# Hall.net
KiCad netlist of a schematic drawn in Altium Designer
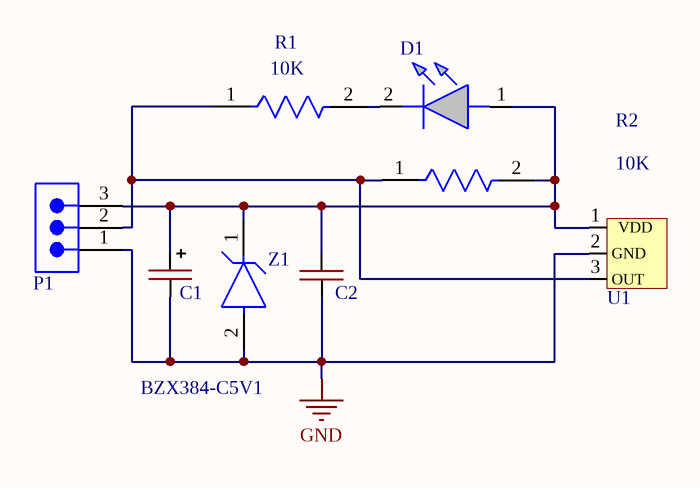
[diagram p0: Hall.SchDoc]

(export (version "E")
  (design (tool "Eeschema 10.0.6"))
  (components
    (comp (ref "C1")
      (value "CAP-POLAR")
      (footprint "CAP-TAN-C")
      (libsource (lib "PASSIVE_COMPONENTS") (part "CAP-POLAR"))
    )
    (comp (ref "C2")
      (value "CAP-NON-POLAR")
      (footprint "CAP-0805")
      (libsource (lib "PASSIVE_COMPONENTS") (part "CAP-NON-POLAR"))
    )
    (comp (ref "D1")
      (value "151031YS06000")
      (footprint "LED_RED")
      (description "WURTH ELEKTRONIK - 151031YS06000 - LED, Yellow, Through Hole, T-1 (3mm), 30 mA, 2 V, 590 nm")
      (fields (field (name "MOUSER PART NUMBER") "710-151031YS06000"))
      (libsource (lib "Optic-LED") (part "LED"))
    )
    (comp (ref "P1")
      (value "61900311021")
      (footprint "61900311021")
      (description "WR-WTB THT Male Left Angled Bottom Locking Header, pitch 2.54mm, 3pins")
      (fields (field (name "MANUFACTURER") "Wurth Elektronik"))
      (libsource (lib "Altium_WR-WTB (rev22b)") (part "61900311021"))
    )
    (comp (ref "R1")
      (value "10K")
      (footprint "RES-0805")
      (libsource (lib "PASSIVE_COMPONENTS") (part "RES-CONST"))
    )
    (comp (ref "R2")
      (value "10K")
      (footprint "RES-0805")
      (libsource (lib "PASSIVE_COMPONENTS") (part "RES-CONST"))
    )
    (comp (ref "U1")
      (value "U1881_Hall")
      (footprint "U1881")
      (libsource (lib "Integrated_Circuts") (part "U1881_Hall"))
    )
    (comp (ref "Z1")
      (value "BZX384-C5V1")
      (footprint "BZX384-SOD323-IPC_C")
      (libsource (lib "Diodes") (part "BZX384-C5V1"))
    )
  )
  (nets
    (net (code "1") (name "GND") (class "Default")
      (node (ref "C1") (pin "2") (pinfunction "-_2") (pintype "passive"))
      (node (ref "C2") (pin "1") (pinfunction "1_1") (pintype "passive"))
      (node (ref "P1") (pin "1") (pinfunction "1_1") (pintype "passive"))
      (node (ref "U1") (pin "2") (pinfunction "GND_2") (pintype "passive"))
      (node (ref "Z1") (pin "2") (pinfunction "A_2") (pintype "passive"))
    )
    (net (code "2") (name "Net-(C1-+)") (class "Default")
      (node (ref "C1") (pin "1") (pinfunction "+_1") (pintype "passive"))
      (node (ref "C2") (pin "2") (pinfunction "2_2") (pintype "passive"))
      (node (ref "D1") (pin "1") (pinfunction "A_1") (pintype "passive"))
      (node (ref "P1") (pin "3") (pinfunction "3_3") (pintype "passive"))
      (node (ref "R2") (pin "2") (pinfunction "2_2") (pintype "passive"))
      (node (ref "U1") (pin "1") (pinfunction "VDD_1") (pintype "passive"))
      (node (ref "Z1") (pin "1") (pinfunction "C_1") (pintype "passive"))
    )
    (net (code "3") (name "Net-(D1-K)") (class "Default")
      (node (ref "D1") (pin "2") (pinfunction "K_2") (pintype "passive"))
      (node (ref "R1") (pin "2") (pinfunction "2_2") (pintype "passive"))
    )
    (net (code "4") (name "Net-(U1-OUT)") (class "Default")
      (node (ref "P1") (pin "2") (pinfunction "2_2") (pintype "passive"))
      (node (ref "R1") (pin "1") (pinfunction "1_1") (pintype "passive"))
      (node (ref "R2") (pin "1") (pinfunction "1_1") (pintype "passive"))
      (node (ref "U1") (pin "3") (pinfunction "OUT_3") (pintype "passive"))
    )
  )
)
